# GD_Tcontroller_PWM.net
KiCad netlist of a schematic drawn in Altium Designer
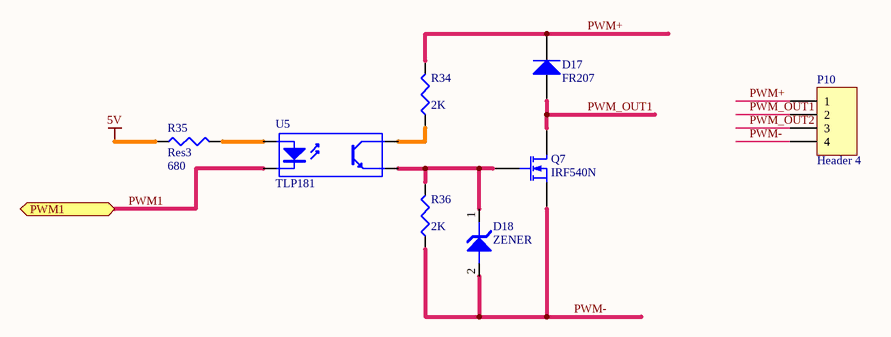
[diagram p0: GD_Tcontroller_PWM.SchDoc]

(export (version "E")
  (design (tool "Eeschema 10.0.6"))
  (components
    (comp (ref "D17")
      (value "FR207")
      (footprint "ONSC-AXIAL_LEAD-2-59AA-01_P")
      (description "Default Diode")
      (fields (field (name "PUBLISHER") "Altium Limited"))
      (libsource (lib "Miscellaneous Devices") (part "Diode"))
    )
    (comp (ref "D18")
      (value "ZENER")
      (footprint "SMB")
      (fields (field (name "MANUFACTURER") "Bourns"))
      (libsource (lib "Enlogic") (part "ZENER"))
    )
    (comp (ref "P10")
      (value "Header 4")
      (footprint "HT5.08-4P-H")
      (description "Header, 4-Pin")
      (fields (field (name "PUBLISHER") "Altium Limited"))
      (libsource (lib "Miscellaneous Connectors") (part "Header 4"))
    )
    (comp (ref "Q7")
      (value "IRF540N")
      (footprint "ONSC-TO-220-3-221A-09_AF")
      (description "N-Channel MOSFET")
      (fields (field (name "PUBLISHER") "Altium Limited"))
      (libsource (lib "Miscellaneous Devices") (part "MOSFET-N"))
    )
    (comp (ref "R34")
      (value "2K")
      (footprint "R1206")
      (description "Resistor")
      (fields (field (name "Comment") "Res3") (field (name "PUBLISHER") "Altium Limited"))
      (libsource (lib "Miscellaneous Devices") (part "Res3"))
    )
    (comp (ref "R35")
      (value "Res3")
      (footprint "R1206")
      (description "Resistor")
      (fields (field (name "ALTIUM_VALUE") "680") (field (name "PUBLISHER") "Altium Limited"))
      (libsource (lib "Miscellaneous Devices") (part "Res3"))
    )
    (comp (ref "R36")
      (value "2K")
      (footprint "R1206")
      (description "Resistor")
      (fields (field (name "Comment") "Res3") (field (name "PUBLISHER") "Altium Limited"))
      (libsource (lib "Miscellaneous Devices") (part "Res3"))
    )
    (comp (ref "U5")
      (value "TLP181")
      (footprint "TLP181")
      (description "4-Pin Phototransistor Optocoupler")
      (fields (field (name "PUBLISHER") "Altium Limited"))
      (libsource (lib "Miscellaneous Devices") (part "Optoisolator1"))
    )
  )
  (nets
    (net (code "1") (name "/PWM+") (class "Default")
      (node (ref "D17") (pin "2") (pinfunction "K_2") (pintype "passive"))
      (node (ref "P10") (pin "1") (pinfunction "1_1") (pintype "passive"))
      (node (ref "R34") (pin "2") (pinfunction "2_2") (pintype "passive"))
    )
    (net (code "2") (name "/PWM-") (class "Default")
      (node (ref "D18") (pin "2") (pintype "passive"))
      (node (ref "P10") (pin "4") (pinfunction "4_4") (pintype "passive"))
      (node (ref "Q7") (pin "3") (pinfunction "S_3") (pintype "passive"))
      (node (ref "R36") (pin "1") (pinfunction "1_1") (pintype "passive"))
    )
    (net (code "3") (name "/PWM1") (class "Default")
      (node (ref "U5") (pin "2") (pinfunction "K_2") (pintype "passive"))
    )
    (net (code "4") (name "/PWM_OUT1") (class "Default")
      (node (ref "D17") (pin "1") (pinfunction "A_1") (pintype "passive"))
      (node (ref "P10") (pin "2") (pinfunction "2_2") (pintype "passive"))
      (node (ref "Q7") (pin "1") (pinfunction "D_1") (pintype "passive"))
    )
    (net (code "5") (name "/PWM_OUT2") (class "Default")
      (node (ref "P10") (pin "3") (pinfunction "3_3") (pintype "passive"))
    )
    (net (code "6") (name "5V") (class "Default")
      (node (ref "R35") (pin "1") (pinfunction "1_1") (pintype "passive"))
    )
    (net (code "7") (name "Net-(Q7-G)") (class "Default")
      (node (ref "D18") (pin "1") (pintype "passive"))
      (node (ref "Q7") (pin "2") (pinfunction "G_2") (pintype "passive"))
      (node (ref "R36") (pin "2") (pinfunction "2_2") (pintype "passive"))
      (node (ref "U5") (pin "3") (pinfunction "E_3") (pintype "passive"))
    )
    (net (code "8") (name "Net-(U5-A)") (class "Default")
      (node (ref "R35") (pin "2") (pinfunction "2_2") (pintype "passive"))
      (node (ref "U5") (pin "1") (pinfunction "A_1") (pintype "passive"))
    )
    (net (code "9") (name "Net-(U5-C)") (class "Default")
      (node (ref "R34") (pin "1") (pinfunction "1_1") (pintype "passive"))
      (node (ref "U5") (pin "4") (pinfunction "C_4") (pintype "passive"))
    )
  )
)
